# RF_PDU.net
KiCad netlist of a schematic drawn in Altium Designer
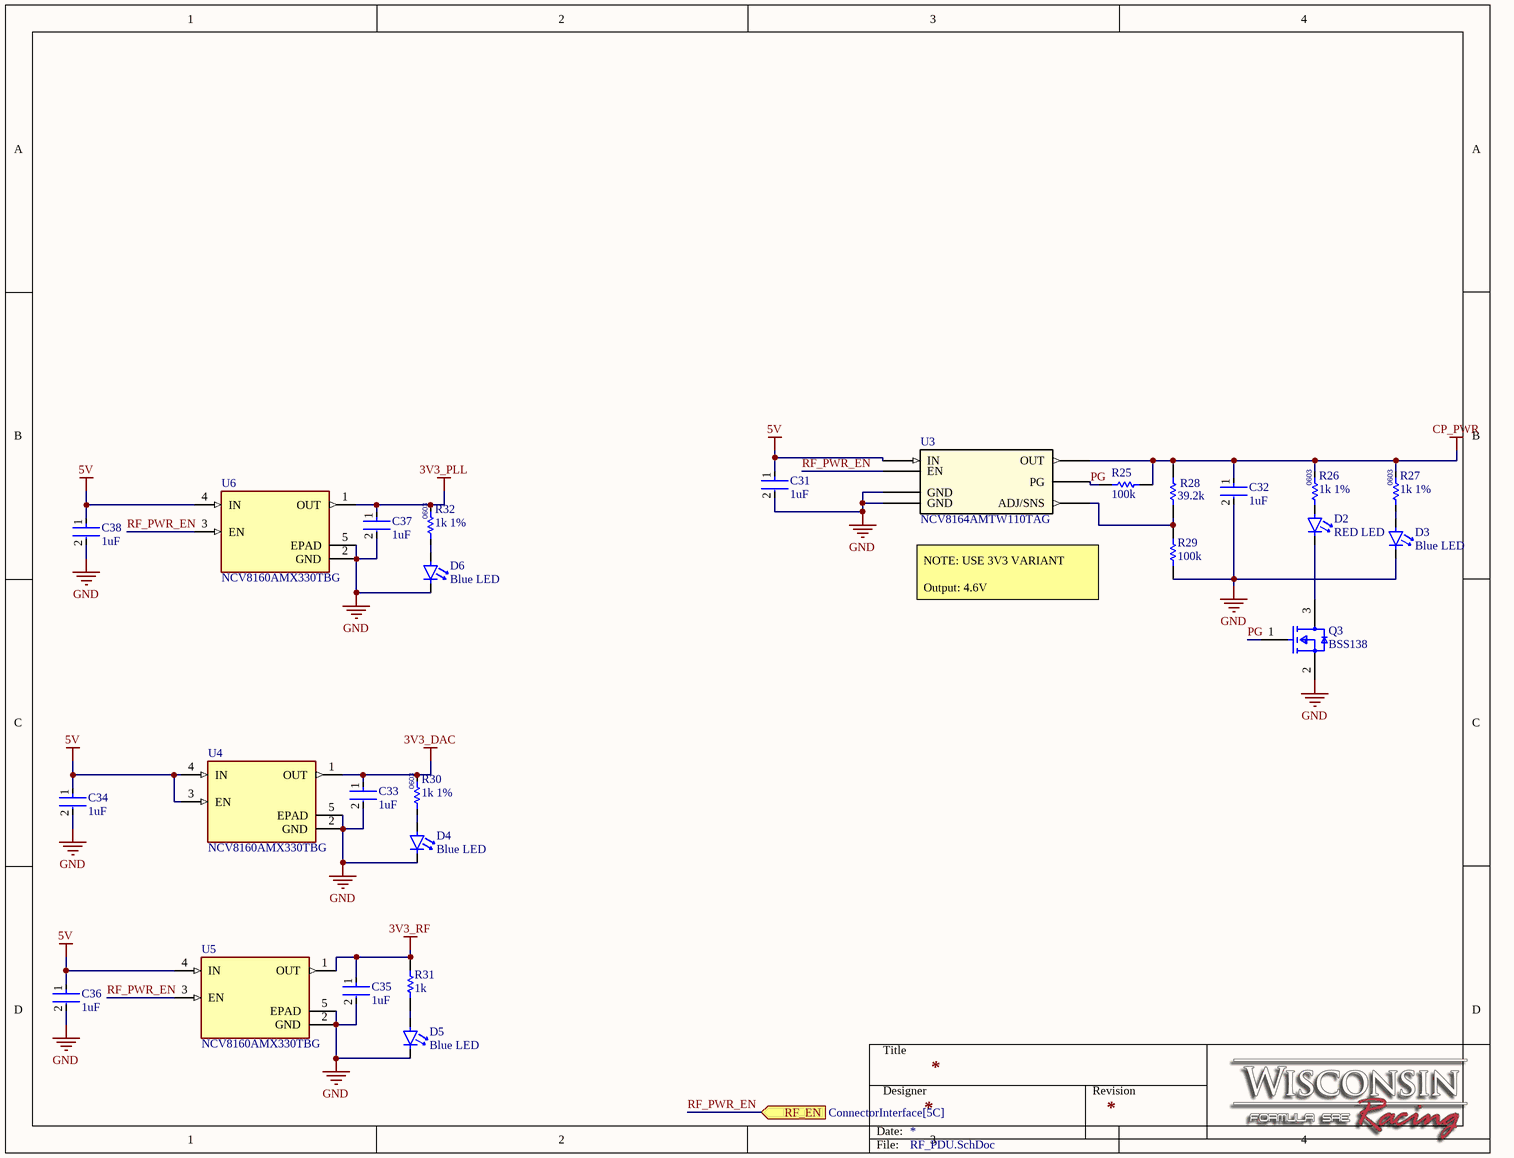
[diagram p0: RF_PDU.SchDoc]

(export (version "E")
  (design (tool "Eeschema 10.0.6"))
  (components
    (comp (ref "C31")
      (value "1uF")
      (footprint "FP-GRM155-0_1-IPC_C")
      (libsource (lib "Altium Content Vault") (part "11868f565c42a9108669ba33697ecf6"))
    )
    (comp (ref "C32")
      (value "1uF")
      (footprint "FP-GRM155-0_1-IPC_C")
      (libsource (lib "Altium Content Vault") (part "11868f565c42a9108669ba33697ecf6"))
    )
    (comp (ref "C33")
      (value "1uF")
      (footprint "FP-GRM155-0_1-IPC_C")
      (libsource (lib "Altium Content Vault") (part "11868f565c42a9108669ba33697ecf6"))
    )
    (comp (ref "C34")
      (value "1uF")
      (footprint "FP-GRM155-0_1-IPC_C")
      (libsource (lib "Altium Content Vault") (part "11868f565c42a9108669ba33697ecf6"))
    )
    (comp (ref "C35")
      (value "1uF")
      (footprint "FP-GRM155-0_1-IPC_C")
      (libsource (lib "Altium Content Vault") (part "11868f565c42a9108669ba33697ecf6"))
    )
    (comp (ref "C36")
      (value "1uF")
      (footprint "FP-GRM155-0_1-IPC_C")
      (libsource (lib "Altium Content Vault") (part "11868f565c42a9108669ba33697ecf6"))
    )
    (comp (ref "C37")
      (value "1uF")
      (footprint "FP-GRM155-0_1-IPC_C")
      (libsource (lib "Altium Content Vault") (part "11868f565c42a9108669ba33697ecf6"))
    )
    (comp (ref "C38")
      (value "1uF")
      (footprint "FP-GRM155-0_1-IPC_C")
      (libsource (lib "Altium Content Vault") (part "11868f565c42a9108669ba33697ecf6"))
    )
    (comp (ref "D2")
      (value "RED LED")
      (footprint "DIOC1608X05N")
      (description "0603 Red SMD Led")
      (libsource (lib "University of Wisconsin Formula FSAE") (part "L196L-LIC-Symbol-1"))
    )
    (comp (ref "D3")
      (value "Blue LED")
      (footprint "0603-LED-1")
      (description "Single Color LED, Blue, Water Clear, 1.1mm")
      (libsource (lib "University of Wisconsin Formula FSAE") (part "LED"))
    )
    (comp (ref "D4")
      (value "Blue LED")
      (footprint "0603-LED-1")
      (description "Single Color LED, Blue, Water Clear, 1.1mm")
      (libsource (lib "University of Wisconsin Formula FSAE") (part "LED"))
    )
    (comp (ref "D5")
      (value "Blue LED")
      (footprint "0603-LED-1")
      (description "Single Color LED, Blue, Water Clear, 1.1mm")
      (libsource (lib "University of Wisconsin Formula FSAE") (part "LED"))
    )
    (comp (ref "D6")
      (value "Blue LED")
      (footprint "0603-LED-1")
      (description "Single Color LED, Blue, Water Clear, 1.1mm")
      (libsource (lib "University of Wisconsin Formula FSAE") (part "LED"))
    )
    (comp (ref "Q3")
      (value "BSS138")
      (footprint "FP-318-08-IPC_B")
      (description "MOSFET N-CH 50V 220MA SOT-23")
      (libsource (lib "Altium Content Vault") (part "3b9c635fedb024a5347a57b145af9cc"))
    )
    (comp (ref "R25")
      (value "100k")
      (footprint "RESC1005X40X25NL05T10")
      (fields (field (name "PART NUMBER") "RC0402FR-07100KL") (field (name "MANUFACTURER") "Yageo / Phycomp"))
      (libsource (lib "Altium Content Vault") (part "RES"))
    )
    (comp (ref "R26")
      (value "1k 1%")
      (footprint "Res0603-type-1")
      (libsource (lib "University of Wisconsin Formula FSAE") (part "RES 0603"))
    )
    (comp (ref "R27")
      (value "1k 1%")
      (footprint "Res0603-type-1")
      (libsource (lib "University of Wisconsin Formula FSAE") (part "RES 0603"))
    )
    (comp (ref "R28")
      (value "39.2k")
      (footprint "RESC1005X40X25ML05T10")
      (fields (field (name "PART NUMBER") "RC0402FR-0739K2L") (field (name "MANUFACTURER") "Yageo"))
      (libsource (lib "Altium Content Vault") (part "RES"))
    )
    (comp (ref "R29")
      (value "100k")
      (footprint "RESC1005X40X25NL05T10")
      (fields (field (name "PART NUMBER") "RC0402FR-07100KL") (field (name "MANUFACTURER") "Yageo / Phycomp"))
      (libsource (lib "Altium Content Vault") (part "RES"))
    )
    (comp (ref "R30")
      (value "1k 1%")
      (footprint "Res0603-type-1")
      (libsource (lib "University of Wisconsin Formula FSAE") (part "RES 0603"))
    )
    (comp (ref "R31")
      (value "1k")
      (footprint "RESC1005X40X25LL05T10")
      (fields (field (name "PART NUMBER") "RC0402JR-071KL") (field (name "MANUFACTURER") "Yageo / Phycomp"))
      (libsource (lib "Altium Content Vault") (part "RES"))
    )
    (comp (ref "R32")
      (value "1k 1%")
      (footprint "Res0603-type-1")
      (libsource (lib "University of Wisconsin Formula FSAE") (part "RES 0603"))
    )
    (comp (ref "U3")
      (value "NCV8164AMTW110TAG")
      (footprint "WDFNW6_511DW_OSI")
      (description "LDO")
      (fields (field (name "COPYRIGHT") "Copyright (C) 2025 Ultra Librarian. All rights reserved."))
      (libsource (lib "University of Wisconsin Formula FSAE") (part "NCV8164AMTW110TAG"))
    )
    (comp (ref "U4")
      (value "NCV8160AMX330TBG")
      (footprint "VREG_NCV8160AMX330TBG")
      (description "Linear Voltage Regulator IC Positive Fixed 1 Output 250mA 4-XDFN (1x1)")
      (fields (field (name "MF") "ON Semiconductor"))
      (libsource (lib "University of Wisconsin Formula FSAE") (part "NCV8160AMX330TBG"))
    )
    (comp (ref "U5")
      (value "NCV8160AMX330TBG")
      (footprint "VREG_NCV8160AMX330TBG")
      (description "Linear Voltage Regulator IC Positive Fixed 1 Output 250mA 4-XDFN (1x1)")
      (fields (field (name "MF") "ON Semiconductor"))
      (libsource (lib "University of Wisconsin Formula FSAE") (part "NCV8160AMX330TBG"))
    )
    (comp (ref "U6")
      (value "NCV8160AMX330TBG")
      (footprint "VREG_NCV8160AMX330TBG")
      (description "Linear Voltage Regulator IC Positive Fixed 1 Output 250mA 4-XDFN (1x1)")
      (fields (field (name "MF") "ON Semiconductor"))
      (libsource (lib "University of Wisconsin Formula FSAE") (part "NCV8160AMX330TBG"))
    )
  )
  (nets
    (net (code "1") (name "/PG") (class "Default")
      (node (ref "Q3") (pin "1") (pinfunction "G_1") (pintype "passive"))
      (node (ref "R25") (pin "2") (pinfunction "2_2") (pintype "passive"))
      (node (ref "U3") (pin "3") (pinfunction "PG_3") (pintype "passive"))
    )
    (net (code "2") (name "/RF_PWR_EN") (class "Default")
      (node (ref "U3") (pin "4") (pinfunction "EN_4") (pintype "passive"))
      (node (ref "U5") (pin "3") (pinfunction "EN_3") (pintype "input"))
      (node (ref "U6") (pin "3") (pinfunction "EN_3") (pintype "input"))
    )
    (net (code "3") (name "3V3_DAC") (class "Default")
      (node (ref "C33") (pin "1") (pinfunction "1_1") (pintype "passive"))
      (node (ref "R30") (pin "2") (pinfunction "2_2") (pintype "passive"))
      (node (ref "U4") (pin "1") (pinfunction "OUT_1") (pintype "output"))
    )
    (net (code "4") (name "3V3_PLL") (class "Default")
      (node (ref "C37") (pin "1") (pinfunction "1_1") (pintype "passive"))
      (node (ref "R32") (pin "2") (pinfunction "2_2") (pintype "passive"))
      (node (ref "U6") (pin "1") (pinfunction "OUT_1") (pintype "output"))
    )
    (net (code "5") (name "3V3_RF") (class "Default")
      (node (ref "C35") (pin "1") (pinfunction "1_1") (pintype "passive"))
      (node (ref "R31") (pin "2") (pinfunction "2_2") (pintype "passive"))
      (node (ref "U5") (pin "1") (pinfunction "OUT_1") (pintype "output"))
    )
    (net (code "6") (name "5V") (class "Default")
      (node (ref "C31") (pin "1") (pinfunction "1_1") (pintype "passive"))
      (node (ref "C34") (pin "1") (pinfunction "1_1") (pintype "passive"))
      (node (ref "C36") (pin "1") (pinfunction "1_1") (pintype "passive"))
      (node (ref "C38") (pin "1") (pinfunction "1_1") (pintype "passive"))
      (node (ref "U3") (pin "6") (pinfunction "IN_6") (pintype "input"))
      (node (ref "U4") (pin "3") (pinfunction "EN_3") (pintype "input"))
      (node (ref "U4") (pin "4") (pinfunction "IN_4") (pintype "input"))
      (node (ref "U5") (pin "4") (pinfunction "IN_4") (pintype "input"))
      (node (ref "U6") (pin "4") (pinfunction "IN_4") (pintype "input"))
    )
    (net (code "7") (name "CP_PWR") (class "Default")
      (node (ref "C32") (pin "1") (pinfunction "1_1") (pintype "passive"))
      (node (ref "R25") (pin "1") (pinfunction "1_1") (pintype "passive"))
      (node (ref "R26") (pin "2") (pinfunction "2_2") (pintype "passive"))
      (node (ref "R27") (pin "2") (pinfunction "2_2") (pintype "passive"))
      (node (ref "R28") (pin "2") (pinfunction "2_2") (pintype "passive"))
      (node (ref "U3") (pin "1") (pinfunction "OUT_1") (pintype "output"))
    )
    (net (code "8") (name "GND") (class "Default")
      (node (ref "C31") (pin "2") (pinfunction "2_2") (pintype "passive"))
      (node (ref "C32") (pin "2") (pinfunction "2_2") (pintype "passive"))
      (node (ref "C33") (pin "2") (pinfunction "2_2") (pintype "passive"))
      (node (ref "C34") (pin "2") (pinfunction "2_2") (pintype "passive"))
      (node (ref "C35") (pin "2") (pinfunction "2_2") (pintype "passive"))
      (node (ref "C36") (pin "2") (pinfunction "2_2") (pintype "passive"))
      (node (ref "C37") (pin "2") (pinfunction "2_2") (pintype "passive"))
      (node (ref "C38") (pin "2") (pinfunction "2_2") (pintype "passive"))
      (node (ref "D3") (pin "1") (pinfunction "C_1") (pintype "passive"))
      (node (ref "D4") (pin "1") (pinfunction "C_1") (pintype "passive"))
      (node (ref "D5") (pin "1") (pinfunction "C_1") (pintype "passive"))
      (node (ref "D6") (pin "1") (pinfunction "C_1") (pintype "passive"))
      (node (ref "Q3") (pin "2") (pinfunction "S_2") (pintype "passive"))
      (node (ref "R29") (pin "1") (pinfunction "1_1") (pintype "passive"))
      (node (ref "U3") (pin "5") (pinfunction "GND_5") (pintype "power_in"))
      (node (ref "U3") (pin "7") (pinfunction "GND_7") (pintype "power_in"))
      (node (ref "U4") (pin "2") (pinfunction "GND_2") (pintype "power_in"))
      (node (ref "U4") (pin "5") (pinfunction "EPAD_5") (pintype "power_in"))
      (node (ref "U5") (pin "2") (pinfunction "GND_2") (pintype "power_in"))
      (node (ref "U5") (pin "5") (pinfunction "EPAD_5") (pintype "power_in"))
      (node (ref "U6") (pin "2") (pinfunction "GND_2") (pintype "power_in"))
      (node (ref "U6") (pin "5") (pinfunction "EPAD_5") (pintype "power_in"))
    )
    (net (code "9") (name "Net-(D2-C)") (class "Default")
      (node (ref "D2") (pin "1") (pinfunction "C_1") (pintype "passive"))
      (node (ref "Q3") (pin "3") (pinfunction "D_3") (pintype "passive"))
    )
    (net (code "10") (name "Net-(D3-A)") (class "Default")
      (node (ref "D3") (pin "2") (pinfunction "A_2") (pintype "passive"))
      (node (ref "R27") (pin "1") (pinfunction "1_1") (pintype "passive"))
    )
    (net (code "11") (name "Net-(D4-A)") (class "Default")
      (node (ref "D4") (pin "2") (pinfunction "A_2") (pintype "passive"))
      (node (ref "R30") (pin "1") (pinfunction "1_1") (pintype "passive"))
    )
    (net (code "12") (name "Net-(D5-A)") (class "Default")
      (node (ref "D5") (pin "2") (pinfunction "A_2") (pintype "passive"))
      (node (ref "R31") (pin "1") (pinfunction "1_1") (pintype "passive"))
    )
    (net (code "13") (name "Net-(D6-A)") (class "Default")
      (node (ref "D6") (pin "2") (pinfunction "A_2") (pintype "passive"))
      (node (ref "R32") (pin "1") (pinfunction "1_1") (pintype "passive"))
    )
    (net (code "14") (name "Net-(U3-ADJ{slash}SNS)") (class "Default")
      (node (ref "R28") (pin "1") (pinfunction "1_1") (pintype "passive"))
      (node (ref "R29") (pin "2") (pinfunction "2_2") (pintype "passive"))
      (node (ref "U3") (pin "2") (pinfunction "ADJ/SNS_2") (pintype "output"))
    )
    (net (code "15") (name "unconnected-(D2-A-Pad2)") (class "Default")
      (node (ref "D2") (pin "2") (pinfunction "A_2") (pintype "passive"))
    )
    (net (code "16") (name "unconnected-(R26-Pad1)") (class "Default")
      (node (ref "R26") (pin "1") (pinfunction "1_1") (pintype "passive"))
    )
  )
)
